# ideaboardv1b-new.net
KiCad netlist of a schematic drawn in EAGLE
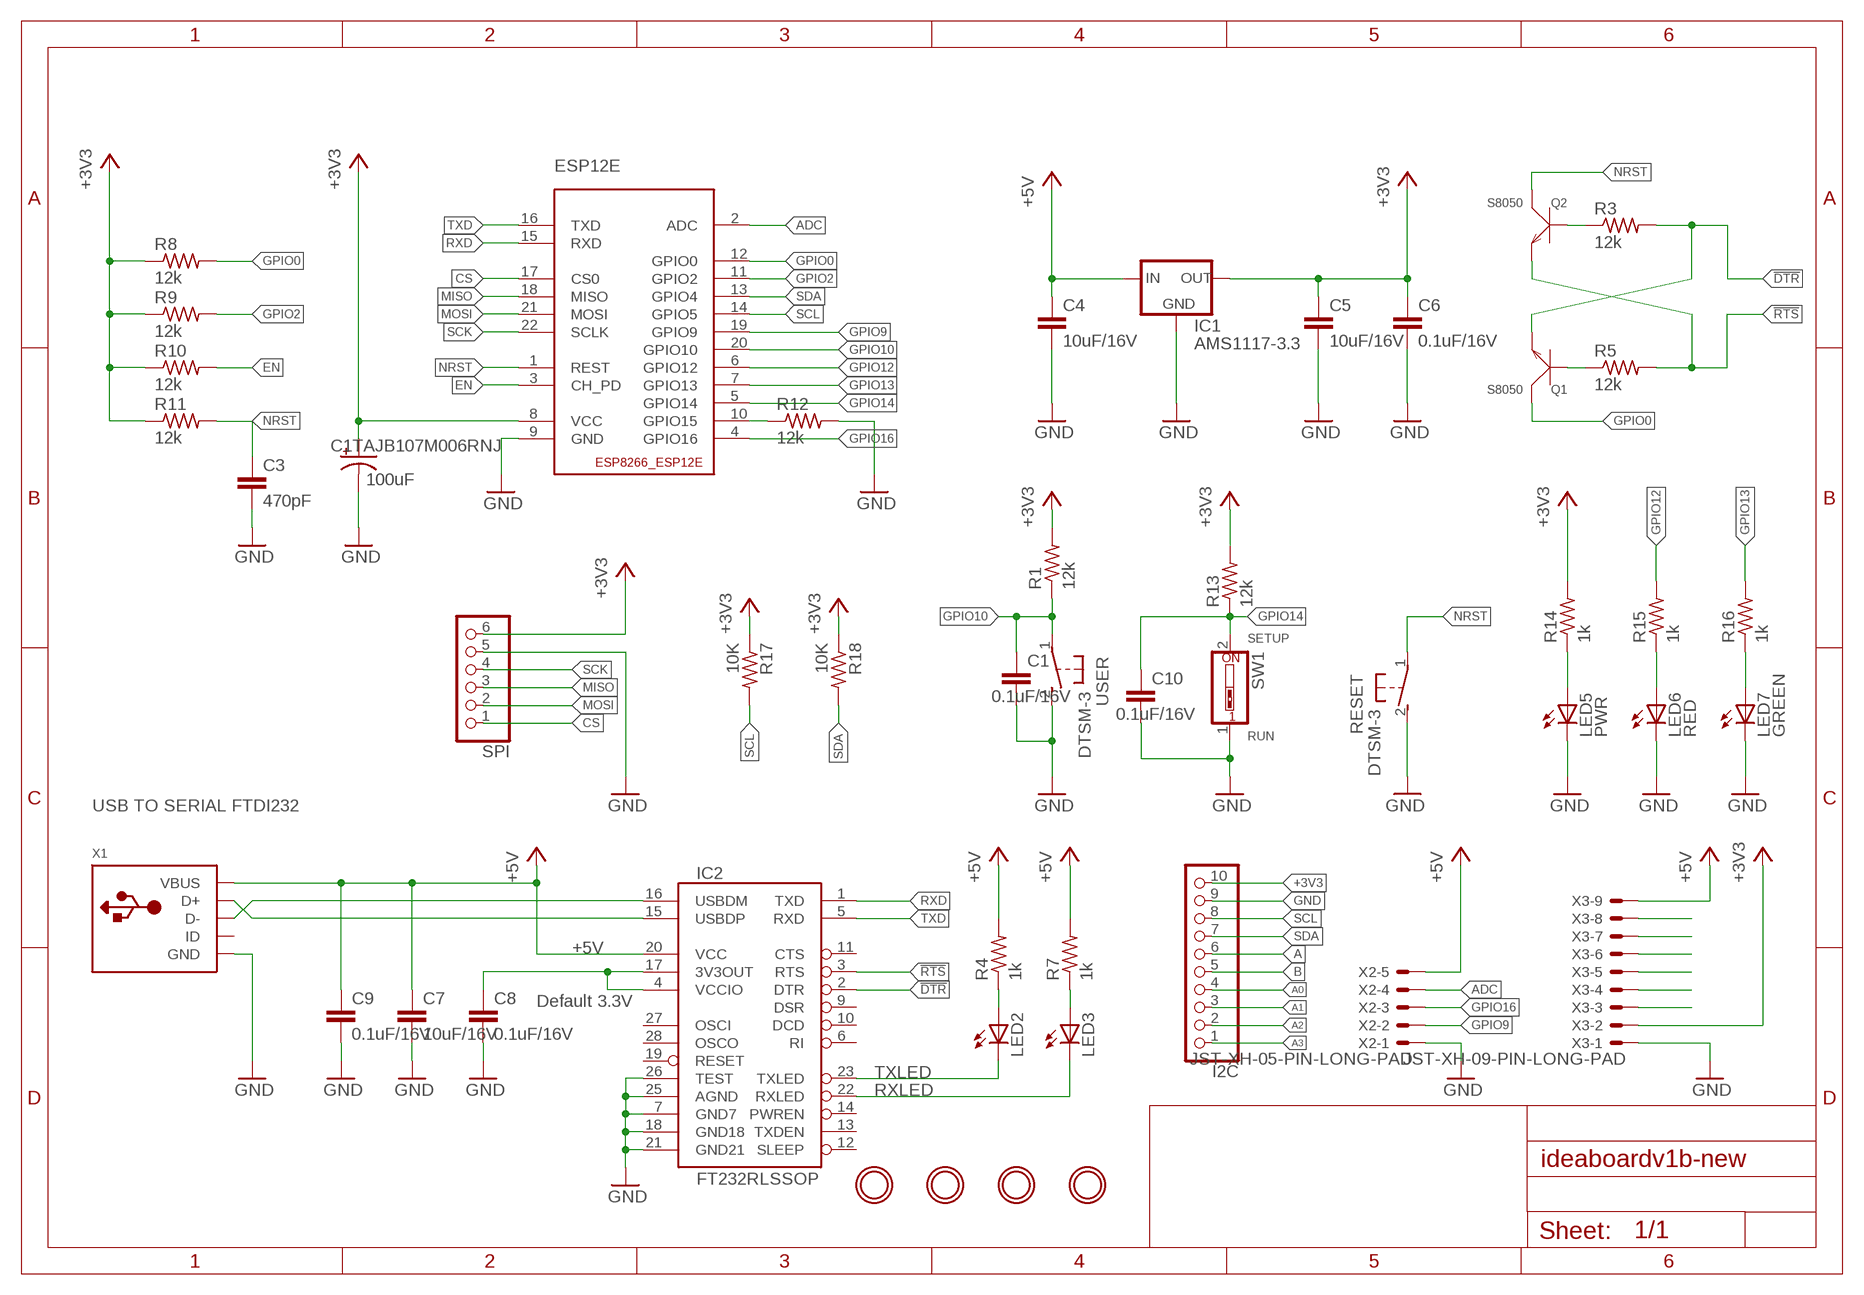
[diagram p0: schematic, sheet 1]

(export (version "E")
  (design (tool "Eeschema 10.0.6"))
  (components
    (comp (ref "C1")
      (value "0.1uF/16V")
      (footprint "eagle-import:C0805K")
      (libsource (lib "eagle-import") (part "C-EUC0805K"))
    )
    (comp (ref "C1TAJB107M006RNJ")
      (value "100uF")
      (footprint "eagle-import:A_3216-18R")
      (libsource (lib "eagle-import") (part "CPOL-USA/3216-18R"))
    )
    (comp (ref "C3")
      (value "470pF")
      (footprint "eagle-import:C0805K")
      (libsource (lib "eagle-import") (part "C-EUC0805K"))
    )
    (comp (ref "C4")
      (value "10uF/16V")
      (footprint "eagle-import:C0805K")
      (libsource (lib "eagle-import") (part "C-EUC0805K"))
    )
    (comp (ref "C5")
      (value "10uF/16V")
      (footprint "eagle-import:C0805K")
      (libsource (lib "eagle-import") (part "C-EUC0805K"))
    )
    (comp (ref "C6")
      (value "0.1uF/16V")
      (footprint "eagle-import:C0805K")
      (libsource (lib "eagle-import") (part "C-EUC0805K"))
    )
    (comp (ref "C7")
      (value "10uF/16V")
      (footprint "eagle-import:C0805K")
      (libsource (lib "eagle-import") (part "C-EUC0805K"))
    )
    (comp (ref "C8")
      (value "0.1uF/16V")
      (footprint "eagle-import:C0805K")
      (libsource (lib "eagle-import") (part "C-EUC0805K"))
    )
    (comp (ref "C9")
      (value "0.1uF/16V")
      (footprint "eagle-import:C0805K")
      (libsource (lib "eagle-import") (part "C-EUC0805K"))
    )
    (comp (ref "C10")
      (value "0.1uF/16V")
      (footprint "eagle-import:C0805K")
      (libsource (lib "eagle-import") (part "C-EUC0805K"))
    )
    (comp (ref "ESP12E")
      (value "ESP8266-12EESP8266-ESP12E")
      (footprint "eagle-import:ESP8266-ESP12E")
      (libsource (lib "eagle-import") (part "ESP8266-12EESP8266-ESP12E"))
    )
    (comp (ref "I2C")
      (value "PINHD-1X10")
      (footprint "eagle-import:1X10")
      (libsource (lib "eagle-import") (part "PINHD-1X10"))
    )
    (comp (ref "IC1")
      (value "AMS1117-3.3")
      (footprint "eagle-import:SOT223")
      (libsource (lib "eagle-import") (part "LM1117"))
    )
    (comp (ref "IC2")
      (value "FT232RLSSOP")
      (footprint "eagle-import:SSOP28DB")
      (libsource (lib "eagle-import") (part "FT232RLSSOP"))
    )
    (comp (ref "LED2")
      (value "LEDCHIP-LED0805")
      (footprint "eagle-import:CHIP-LED0805")
      (libsource (lib "eagle-import") (part "LEDCHIP-LED0805"))
    )
    (comp (ref "LED3")
      (value "LEDCHIP-LED0805")
      (footprint "eagle-import:CHIP-LED0805")
      (libsource (lib "eagle-import") (part "LEDCHIP-LED0805"))
    )
    (comp (ref "LED5")
      (value "PWR")
      (footprint "eagle-import:CHIP-LED0805")
      (libsource (lib "eagle-import") (part "LEDCHIP-LED0805"))
    )
    (comp (ref "LED6")
      (value "RED")
      (footprint "eagle-import:CHIP-LED0805")
      (libsource (lib "eagle-import") (part "LEDCHIP-LED0805"))
    )
    (comp (ref "LED7")
      (value "GREEN")
      (footprint "eagle-import:CHIP-LED0805")
      (libsource (lib "eagle-import") (part "LEDCHIP-LED0805"))
    )
    (comp (ref "Q1")
      (value "S8050")
      (footprint "eagle-import:SOT-23")
      (fields (field (name "MF") "JCET"))
      (libsource (lib "eagle-import") (part "SMD-TRANSISTORS-NPN-25V-500MW(SOT-23)"))
    )
    (comp (ref "Q2")
      (value "S8050")
      (footprint "eagle-import:SOT-23")
      (fields (field (name "MF") "JCET"))
      (libsource (lib "eagle-import") (part "SMD-TRANSISTORS-NPN-25V-500MW(SOT-23)"))
    )
    (comp (ref "R1")
      (value "12k")
      (footprint "eagle-import:M0805")
      (libsource (lib "eagle-import") (part "R-US_M0805"))
    )
    (comp (ref "R3")
      (value "12k")
      (footprint "eagle-import:M0805")
      (libsource (lib "eagle-import") (part "R-US_M0805"))
    )
    (comp (ref "R4")
      (value "1k")
      (footprint "eagle-import:M0805")
      (libsource (lib "eagle-import") (part "R-US_M0805"))
    )
    (comp (ref "R5")
      (value "12k")
      (footprint "eagle-import:M0805")
      (libsource (lib "eagle-import") (part "R-US_M0805"))
    )
    (comp (ref "R7")
      (value "1k")
      (footprint "eagle-import:M0805")
      (libsource (lib "eagle-import") (part "R-US_M0805"))
    )
    (comp (ref "R8")
      (value "12k")
      (footprint "eagle-import:M0805")
      (libsource (lib "eagle-import") (part "R-US_M0805"))
    )
    (comp (ref "R9")
      (value "12k")
      (footprint "eagle-import:M0805")
      (libsource (lib "eagle-import") (part "R-US_M0805"))
    )
    (comp (ref "R10")
      (value "12k")
      (footprint "eagle-import:M0805")
      (libsource (lib "eagle-import") (part "R-US_M0805"))
    )
    (comp (ref "R11")
      (value "12k")
      (footprint "eagle-import:M0805")
      (libsource (lib "eagle-import") (part "R-US_M0805"))
    )
    (comp (ref "R12")
      (value "12k")
      (footprint "eagle-import:M0805")
      (libsource (lib "eagle-import") (part "R-US_M0805"))
    )
    (comp (ref "R13")
      (value "12k")
      (footprint "eagle-import:M0805")
      (libsource (lib "eagle-import") (part "R-US_M0805"))
    )
    (comp (ref "R14")
      (value "1k")
      (footprint "eagle-import:M0805")
      (libsource (lib "eagle-import") (part "R-US_M0805"))
    )
    (comp (ref "R15")
      (value "1k")
      (footprint "eagle-import:M0805")
      (libsource (lib "eagle-import") (part "R-US_M0805"))
    )
    (comp (ref "R16")
      (value "1k")
      (footprint "eagle-import:M0805")
      (libsource (lib "eagle-import") (part "R-US_M0805"))
    )
    (comp (ref "R17")
      (value "10K")
      (footprint "eagle-import:M0805")
      (libsource (lib "eagle-import") (part "R-US_M0805"))
    )
    (comp (ref "R18")
      (value "10K")
      (footprint "eagle-import:M0805")
      (libsource (lib "eagle-import") (part "R-US_M0805"))
    )
    (comp (ref "RESET")
      (value "DTSM-3")
      (footprint "eagle-import:DTSM-3")
      (libsource (lib "eagle-import") (part "DTSM-3"))
    )
    (comp (ref "SPI")
      (value "PINHD-1X6")
      (footprint "eagle-import:1X06")
      (libsource (lib "eagle-import") (part "PINHD-1X6"))
    )
    (comp (ref "SW1")
      (value "SW_DIP-1")
      (footprint "eagle-import:EDG-01")
      (libsource (lib "eagle-import") (part "SW_DIP-1"))
    )
    (comp (ref "U$1")
      (value "MOUNTINGHOLE2.0")
      (footprint "eagle-import:MOUNTINGHOLE_2.0_PLATED")
      (libsource (lib "eagle-import") (part "MOUNTINGHOLE2.0"))
    )
    (comp (ref "U$2")
      (value "MOUNTINGHOLE2.0")
      (footprint "eagle-import:MOUNTINGHOLE_2.0_PLATED")
      (libsource (lib "eagle-import") (part "MOUNTINGHOLE2.0"))
    )
    (comp (ref "U$3")
      (value "MOUNTINGHOLE2.0")
      (footprint "eagle-import:MOUNTINGHOLE_2.0_PLATED")
      (libsource (lib "eagle-import") (part "MOUNTINGHOLE2.0"))
    )
    (comp (ref "U$4")
      (value "MOUNTINGHOLE2.0")
      (footprint "eagle-import:MOUNTINGHOLE_2.0_PLATED")
      (libsource (lib "eagle-import") (part "MOUNTINGHOLE2.0"))
    )
    (comp (ref "USER")
      (value "DTSM-3")
      (footprint "eagle-import:DTSM-3")
      (libsource (lib "eagle-import") (part "DTSM-3"))
    )
    (comp (ref "X1")
      (value "USB_MICRO_20329_V2")
      (footprint "eagle-import:4UCONN_20329_V2")
      (libsource (lib "eagle-import") (part "USB_MICRO_20329_V2"))
    )
    (comp (ref "X2")
      (value "JST-XH-05-PIN-LONG-PAD")
      (footprint "eagle-import:JST-XH-05-PACKAGE-LONG-PAD")
      (libsource (lib "eagle-import") (part "JST-XH-05-PIN-LONG-PAD"))
    )
    (comp (ref "X3")
      (value "JST-XH-09-PIN-LONG-PAD")
      (footprint "eagle-import:JST-XH-09-PACKAGE-LONG-PAD")
      (libsource (lib "eagle-import") (part "JST-XH-09-PIN-LONG-PAD"))
    )
  )
  (nets
    (net (code "1") (name "+3V3") (class "Default")
      (node (ref "C1TAJB107M006RNJ") (pin "+") (pinfunction "+_+") (pintype "passive"))
      (node (ref "C5") (pin "1") (pinfunction "1_1") (pintype "passive"))
      (node (ref "C6") (pin "1") (pinfunction "1_1") (pintype "passive"))
      (node (ref "ESP12E") (pin "8") (pinfunction "VCC_8") (pintype "bidirectional"))
      (node (ref "I2C") (pin "10") (pinfunction "10_10") (pintype "passive"))
      (node (ref "IC1") (pin "2") (pinfunction "OUT_2") (pintype "passive"))
      (node (ref "R1") (pin "2") (pinfunction "2_2") (pintype "passive"))
      (node (ref "R10") (pin "1") (pinfunction "1_1") (pintype "passive"))
      (node (ref "R11") (pin "1") (pinfunction "1_1") (pintype "passive"))
      (node (ref "R13") (pin "2") (pinfunction "2_2") (pintype "passive"))
      (node (ref "R14") (pin "2") (pinfunction "2_2") (pintype "passive"))
      (node (ref "R17") (pin "1") (pinfunction "1_1") (pintype "passive"))
      (node (ref "R18") (pin "1") (pinfunction "1_1") (pintype "passive"))
      (node (ref "R8") (pin "1") (pinfunction "1_1") (pintype "passive"))
      (node (ref "R9") (pin "1") (pinfunction "1_1") (pintype "passive"))
      (node (ref "SPI") (pin "6") (pinfunction "6_6") (pintype "passive"))
      (node (ref "X3") (pin "2") (pinfunction "S_2") (pintype "passive"))
    )
    (net (code "2") (name "+5V") (class "Default")
      (node (ref "C4") (pin "1") (pinfunction "1_1") (pintype "passive"))
      (node (ref "C7") (pin "1") (pinfunction "1_1") (pintype "passive"))
      (node (ref "C9") (pin "1") (pinfunction "1_1") (pintype "passive"))
      (node (ref "IC1") (pin "3") (pinfunction "IN_3") (pintype "input"))
      (node (ref "IC2") (pin "20") (pinfunction "VCC_20") (pintype "power_in"))
      (node (ref "R4") (pin "2") (pinfunction "2_2") (pintype "passive"))
      (node (ref "R7") (pin "2") (pinfunction "2_2") (pintype "passive"))
      (node (ref "X1") (pin "VBUS") (pinfunction "VBUS_VBUS") (pintype "power_in"))
      (node (ref "X2") (pin "5") (pinfunction "S_5") (pintype "passive"))
      (node (ref "X3") (pin "9") (pinfunction "S_9") (pintype "passive"))
    )
    (net (code "3") (name "/RXLED") (class "Default")
      (node (ref "IC2") (pin "22") (pinfunction "RXLED_22") (pintype "input"))
      (node (ref "LED3") (pin "C") (pinfunction "C_C") (pintype "passive"))
    )
    (net (code "4") (name "/TXLED") (class "Default")
      (node (ref "IC2") (pin "23") (pinfunction "TXLED_23") (pintype "input"))
      (node (ref "LED2") (pin "C") (pinfunction "C_C") (pintype "passive"))
    )
    (net (code "5") (name "/~{DTR}") (class "Default")
      (node (ref "IC2") (pin "2") (pinfunction "DTR_2") (pintype "output"))
      (node (ref "Q1") (pin "2") (pinfunction "E_2") (pintype "passive"))
      (node (ref "R3") (pin "2") (pinfunction "2_2") (pintype "passive"))
    )
    (net (code "6") (name "/~{RTS}") (class "Default")
      (node (ref "IC2") (pin "3") (pinfunction "RTS_3") (pintype "output"))
      (node (ref "Q2") (pin "2") (pinfunction "E_2") (pintype "passive"))
      (node (ref "R5") (pin "2") (pinfunction "2_2") (pintype "passive"))
    )
    (net (code "7") (name "A") (class "Default")
      (node (ref "I2C") (pin "6") (pinfunction "6_6") (pintype "passive"))
      (node (ref "X3") (pin "3") (pinfunction "S_3") (pintype "passive"))
    )
    (net (code "8") (name "A0") (class "Default")
      (node (ref "I2C") (pin "4") (pinfunction "4_4") (pintype "passive"))
      (node (ref "X3") (pin "5") (pinfunction "S_5") (pintype "passive"))
    )
    (net (code "9") (name "A1") (class "Default")
      (node (ref "I2C") (pin "3") (pinfunction "3_3") (pintype "passive"))
      (node (ref "X3") (pin "6") (pinfunction "S_6") (pintype "passive"))
    )
    (net (code "10") (name "A2") (class "Default")
      (node (ref "I2C") (pin "2") (pinfunction "2_2") (pintype "passive"))
      (node (ref "X3") (pin "7") (pinfunction "S_7") (pintype "passive"))
    )
    (net (code "11") (name "A3") (class "Default")
      (node (ref "I2C") (pin "1") (pinfunction "1_1") (pintype "passive"))
      (node (ref "X3") (pin "8") (pinfunction "S_8") (pintype "passive"))
    )
    (net (code "12") (name "ADC") (class "Default")
      (node (ref "ESP12E") (pin "2") (pinfunction "ADC_2") (pintype "bidirectional"))
      (node (ref "X2") (pin "4") (pinfunction "S_4") (pintype "passive"))
    )
    (net (code "13") (name "B") (class "Default")
      (node (ref "I2C") (pin "5") (pinfunction "5_5") (pintype "passive"))
      (node (ref "X3") (pin "4") (pinfunction "S_4") (pintype "passive"))
    )
    (net (code "14") (name "CS") (class "Default")
      (node (ref "ESP12E") (pin "17") (pinfunction "CS0_17") (pintype "bidirectional"))
      (node (ref "SPI") (pin "1") (pinfunction "1_1") (pintype "passive"))
    )
    (net (code "15") (name "EN") (class "Default")
      (node (ref "ESP12E") (pin "3") (pinfunction "CH_PD_3") (pintype "bidirectional"))
      (node (ref "R10") (pin "2") (pinfunction "2_2") (pintype "passive"))
    )
    (net (code "16") (name "GND") (class "Default")
      (node (ref "C1") (pin "2") (pinfunction "2_2") (pintype "passive"))
      (node (ref "C10") (pin "2") (pinfunction "2_2") (pintype "passive"))
      (node (ref "C1TAJB107M006RNJ") (pin "-") (pinfunction "-_-") (pintype "passive"))
      (node (ref "C3") (pin "2") (pinfunction "2_2") (pintype "passive"))
      (node (ref "C4") (pin "2") (pinfunction "2_2") (pintype "passive"))
      (node (ref "C5") (pin "2") (pinfunction "2_2") (pintype "passive"))
      (node (ref "C6") (pin "2") (pinfunction "2_2") (pintype "passive"))
      (node (ref "C7") (pin "2") (pinfunction "2_2") (pintype "passive"))
      (node (ref "C8") (pin "2") (pinfunction "2_2") (pintype "passive"))
      (node (ref "C9") (pin "2") (pinfunction "2_2") (pintype "passive"))
      (node (ref "ESP12E") (pin "9") (pinfunction "GND_9") (pintype "bidirectional"))
      (node (ref "I2C") (pin "9") (pinfunction "9_9") (pintype "passive"))
      (node (ref "IC1") (pin "1") (pinfunction "GND_1") (pintype "input"))
      (node (ref "IC2") (pin "18") (pinfunction "GND18_18") (pintype "power_in"))
      (node (ref "IC2") (pin "21") (pinfunction "GND21_21") (pintype "power_in"))
      (node (ref "IC2") (pin "25") (pinfunction "AGND_25") (pintype "power_in"))
      (node (ref "IC2") (pin "26") (pinfunction "TEST_26") (pintype "input"))
      (node (ref "IC2") (pin "7") (pinfunction "GND7_7") (pintype "power_in"))
      (node (ref "LED5") (pin "C") (pinfunction "C_C") (pintype "passive"))
      (node (ref "LED6") (pin "C") (pinfunction "C_C") (pintype "passive"))
      (node (ref "LED7") (pin "C") (pinfunction "C_C") (pintype "passive"))
      (node (ref "R12") (pin "2") (pinfunction "2_2") (pintype "passive"))
      (node (ref "RESET") (pin "2") (pinfunction "2_2") (pintype "passive"))
      (node (ref "SPI") (pin "5") (pinfunction "5_5") (pintype "passive"))
      (node (ref "SW1") (pin "1") (pinfunction "1_1") (pintype "passive"))
      (node (ref "USER") (pin "2") (pinfunction "2_2") (pintype "passive"))
      (node (ref "X1") (pin "BASE@1") (pinfunction "GND_BASE@1") (pintype "power_in"))
      (node (ref "X1") (pin "BASE@2") (pinfunction "GND_BASE@2") (pintype "power_in"))
      (node (ref "X1") (pin "GND") (pinfunction "GND_GND") (pintype "power_in"))
      (node (ref "X1") (pin "SPRT@1") (pinfunction "GND_SPRT@1") (pintype "power_in"))
      (node (ref "X1") (pin "SPRT@2") (pinfunction "GND_SPRT@2") (pintype "power_in"))
      (node (ref "X1") (pin "SPRT@3") (pinfunction "GND_SPRT@3") (pintype "power_in"))
      (node (ref "X1") (pin "SPRT@4") (pinfunction "GND_SPRT@4") (pintype "power_in"))
      (node (ref "X2") (pin "1") (pinfunction "S_1") (pintype "passive"))
      (node (ref "X3") (pin "1") (pinfunction "S_1") (pintype "passive"))
    )
    (net (code "17") (name "GPIO0") (class "Default")
      (node (ref "ESP12E") (pin "12") (pinfunction "GPIO0_12") (pintype "bidirectional"))
      (node (ref "Q1") (pin "3") (pinfunction "C_3") (pintype "passive"))
      (node (ref "R8") (pin "2") (pinfunction "2_2") (pintype "passive"))
    )
    (net (code "18") (name "GPIO2") (class "Default")
      (node (ref "ESP12E") (pin "11") (pinfunction "GPIO2_11") (pintype "bidirectional"))
      (node (ref "R9") (pin "2") (pinfunction "2_2") (pintype "passive"))
    )
    (net (code "19") (name "GPIO9") (class "Default")
      (node (ref "ESP12E") (pin "19") (pinfunction "GPIO9_19") (pintype "bidirectional"))
      (node (ref "X2") (pin "2") (pinfunction "S_2") (pintype "passive"))
    )
    (net (code "20") (name "GPIO10") (class "Default")
      (node (ref "C1") (pin "1") (pinfunction "1_1") (pintype "passive"))
      (node (ref "ESP12E") (pin "20") (pinfunction "GPIO10_20") (pintype "bidirectional"))
      (node (ref "R1") (pin "1") (pinfunction "1_1") (pintype "passive"))
      (node (ref "USER") (pin "1") (pinfunction "1_1") (pintype "passive"))
    )
    (net (code "21") (name "GPIO12") (class "Default")
      (node (ref "ESP12E") (pin "6") (pinfunction "GPIO12_6") (pintype "bidirectional"))
      (node (ref "R15") (pin "2") (pinfunction "2_2") (pintype "passive"))
    )
    (net (code "22") (name "GPIO13") (class "Default")
      (node (ref "ESP12E") (pin "7") (pinfunction "GPIO13_7") (pintype "bidirectional"))
      (node (ref "R16") (pin "2") (pinfunction "2_2") (pintype "passive"))
    )
    (net (code "23") (name "GPIO14") (class "Default")
      (node (ref "C10") (pin "1") (pinfunction "1_1") (pintype "passive"))
      (node (ref "ESP12E") (pin "5") (pinfunction "GPIO14_5") (pintype "bidirectional"))
      (node (ref "R13") (pin "1") (pinfunction "1_1") (pintype "passive"))
      (node (ref "SW1") (pin "2") (pinfunction "2_2") (pintype "passive"))
    )
    (net (code "24") (name "GPIO16") (class "Default")
      (node (ref "ESP12E") (pin "4") (pinfunction "GPIO16_4") (pintype "bidirectional"))
      (node (ref "X2") (pin "3") (pinfunction "S_3") (pintype "passive"))
    )
    (net (code "25") (name "MISO") (class "Default")
      (node (ref "ESP12E") (pin "18") (pinfunction "MISO_18") (pintype "bidirectional"))
      (node (ref "SPI") (pin "3") (pinfunction "3_3") (pintype "passive"))
    )
    (net (code "26") (name "MOSI") (class "Default")
      (node (ref "ESP12E") (pin "21") (pinfunction "MOSI_21") (pintype "bidirectional"))
      (node (ref "SPI") (pin "2") (pinfunction "2_2") (pintype "passive"))
    )
    (net (code "27") (name "NRST") (class "Default")
      (node (ref "C3") (pin "1") (pinfunction "1_1") (pintype "passive"))
      (node (ref "ESP12E") (pin "1") (pinfunction "REST_1") (pintype "bidirectional"))
      (node (ref "Q2") (pin "3") (pinfunction "C_3") (pintype "passive"))
      (node (ref "R11") (pin "2") (pinfunction "2_2") (pintype "passive"))
      (node (ref "RESET") (pin "1") (pinfunction "1_1") (pintype "passive"))
    )
    (net (code "28") (name "Net-(ESP12E-GPIO15)") (class "Default")
      (node (ref "ESP12E") (pin "10") (pinfunction "GPIO15_10") (pintype "bidirectional"))
      (node (ref "R12") (pin "1") (pinfunction "1_1") (pintype "passive"))
    )
    (net (code "29") (name "Net-(IC2-3V3OUT)") (class "Default")
      (node (ref "C8") (pin "1") (pinfunction "1_1") (pintype "passive"))
      (node (ref "IC2") (pin "17") (pinfunction "3V3OUT_17") (pintype "output"))
      (node (ref "IC2") (pin "4") (pinfunction "VCCIO_4") (pintype "power_in"))
    )
    (net (code "30") (name "Net-(IC2-USBDM)") (class "Default")
      (node (ref "IC2") (pin "16") (pinfunction "USBDM_16") (pintype "bidirectional"))
      (node (ref "X1") (pin "D-") (pinfunction "D-_D-") (pintype "bidirectional"))
    )
    (net (code "31") (name "Net-(IC2-USBDP)") (class "Default")
      (node (ref "IC2") (pin "15") (pinfunction "USBDP_15") (pintype "bidirectional"))
      (node (ref "X1") (pin "D+") (pinfunction "D+_D+") (pintype "bidirectional"))
    )
    (net (code "32") (name "Net-(LED2-PadA)") (class "Default")
      (node (ref "LED2") (pin "A") (pinfunction "A_A") (pintype "passive"))
      (node (ref "R4") (pin "1") (pinfunction "1_1") (pintype "passive"))
    )
    (net (code "33") (name "Net-(LED3-PadA)") (class "Default")
      (node (ref "LED3") (pin "A") (pinfunction "A_A") (pintype "passive"))
      (node (ref "R7") (pin "1") (pinfunction "1_1") (pintype "passive"))
    )
    (net (code "34") (name "Net-(LED5-PadA)") (class "Default")
      (node (ref "LED5") (pin "A") (pinfunction "A_A") (pintype "passive"))
      (node (ref "R14") (pin "1") (pinfunction "1_1") (pintype "passive"))
    )
    (net (code "35") (name "Net-(LED6-PadA)") (class "Default")
      (node (ref "LED6") (pin "A") (pinfunction "A_A") (pintype "passive"))
      (node (ref "R15") (pin "1") (pinfunction "1_1") (pintype "passive"))
    )
    (net (code "36") (name "Net-(LED7-PadA)") (class "Default")
      (node (ref "LED7") (pin "A") (pinfunction "A_A") (pintype "passive"))
      (node (ref "R16") (pin "1") (pinfunction "1_1") (pintype "passive"))
    )
    (net (code "37") (name "Net-(Q1-B)") (class "Default")
      (node (ref "Q1") (pin "1") (pinfunction "B_1") (pintype "passive"))
      (node (ref "R5") (pin "1") (pinfunction "1_1") (pintype "passive"))
    )
    (net (code "38") (name "Net-(Q2-B)") (class "Default")
      (node (ref "Q2") (pin "1") (pinfunction "B_1") (pintype "passive"))
      (node (ref "R3") (pin "1") (pinfunction "1_1") (pintype "passive"))
    )
    (net (code "39") (name "RXD") (class "Default")
      (node (ref "ESP12E") (pin "15") (pinfunction "RXD_15") (pintype "bidirectional"))
      (node (ref "IC2") (pin "1") (pinfunction "TXD_1") (pintype "output"))
    )
    (net (code "40") (name "SCK") (class "Default")
      (node (ref "ESP12E") (pin "22") (pinfunction "SCLK_22") (pintype "bidirectional"))
      (node (ref "SPI") (pin "4") (pinfunction "4_4") (pintype "passive"))
    )
    (net (code "41") (name "SCL") (class "Default")
      (node (ref "ESP12E") (pin "14") (pinfunction "GPIO5_14") (pintype "bidirectional"))
      (node (ref "I2C") (pin "8") (pinfunction "8_8") (pintype "passive"))
      (node (ref "R17") (pin "2") (pinfunction "2_2") (pintype "passive"))
    )
    (net (code "42") (name "SDA") (class "Default")
      (node (ref "ESP12E") (pin "13") (pinfunction "GPIO4_13") (pintype "bidirectional"))
      (node (ref "I2C") (pin "7") (pinfunction "7_7") (pintype "passive"))
      (node (ref "R18") (pin "2") (pinfunction "2_2") (pintype "passive"))
    )
    (net (code "43") (name "TXD") (class "Default")
      (node (ref "ESP12E") (pin "16") (pinfunction "TXD_16") (pintype "bidirectional"))
      (node (ref "IC2") (pin "5") (pinfunction "RXD_5") (pintype "input"))
    )
    (net (code "44") (name "unconnected-(IC2-CTS-Pad11)") (class "Default")
      (node (ref "IC2") (pin "11") (pinfunction "CTS_11") (pintype "input"))
    )
    (net (code "45") (name "unconnected-(IC2-DCD-Pad10)") (class "Default")
      (node (ref "IC2") (pin "10") (pinfunction "DCD_10") (pintype "input"))
    )
    (net (code "46") (name "unconnected-(IC2-DSR-Pad9)") (class "Default")
      (node (ref "IC2") (pin "9") (pinfunction "DSR_9") (pintype "input"))
    )
    (net (code "47") (name "unconnected-(IC2-OSCI-Pad27)") (class "Default")
      (node (ref "IC2") (pin "27") (pinfunction "OSCI_27") (pintype "input"))
    )
    (net (code "48") (name "unconnected-(IC2-OSCO-Pad28)") (class "Default")
      (node (ref "IC2") (pin "28") (pinfunction "OSCO_28") (pintype "output"))
    )
    (net (code "49") (name "unconnected-(IC2-PWREN-Pad14)") (class "Default")
      (node (ref "IC2") (pin "14") (pinfunction "PWREN_14") (pintype "input"))
    )
    (net (code "50") (name "unconnected-(IC2-RESET-Pad19)") (class "Default")
      (node (ref "IC2") (pin "19") (pinfunction "RESET_19") (pintype "input"))
    )
    (net (code "51") (name "unconnected-(IC2-RI-Pad6)") (class "Default")
      (node (ref "IC2") (pin "6") (pinfunction "RI_6") (pintype "input"))
    )
    (net (code "52") (name "unconnected-(IC2-SLEEP-Pad12)") (class "Default")
      (node (ref "IC2") (pin "12") (pinfunction "SLEEP_12") (pintype "input"))
    )
    (net (code "53") (name "unconnected-(IC2-TXDEN-Pad13)") (class "Default")
      (node (ref "IC2") (pin "13") (pinfunction "TXDEN_13") (pintype "input"))
    )
    (net (code "54") (name "unconnected-(X1-PadID)") (class "Default")
      (node (ref "X1") (pin "ID") (pinfunction "ID_ID") (pintype "bidirectional"))
    )
  )
)
